# myPLA_Tester_shield.net
KiCad netlist of a schematic drawn in EAGLE
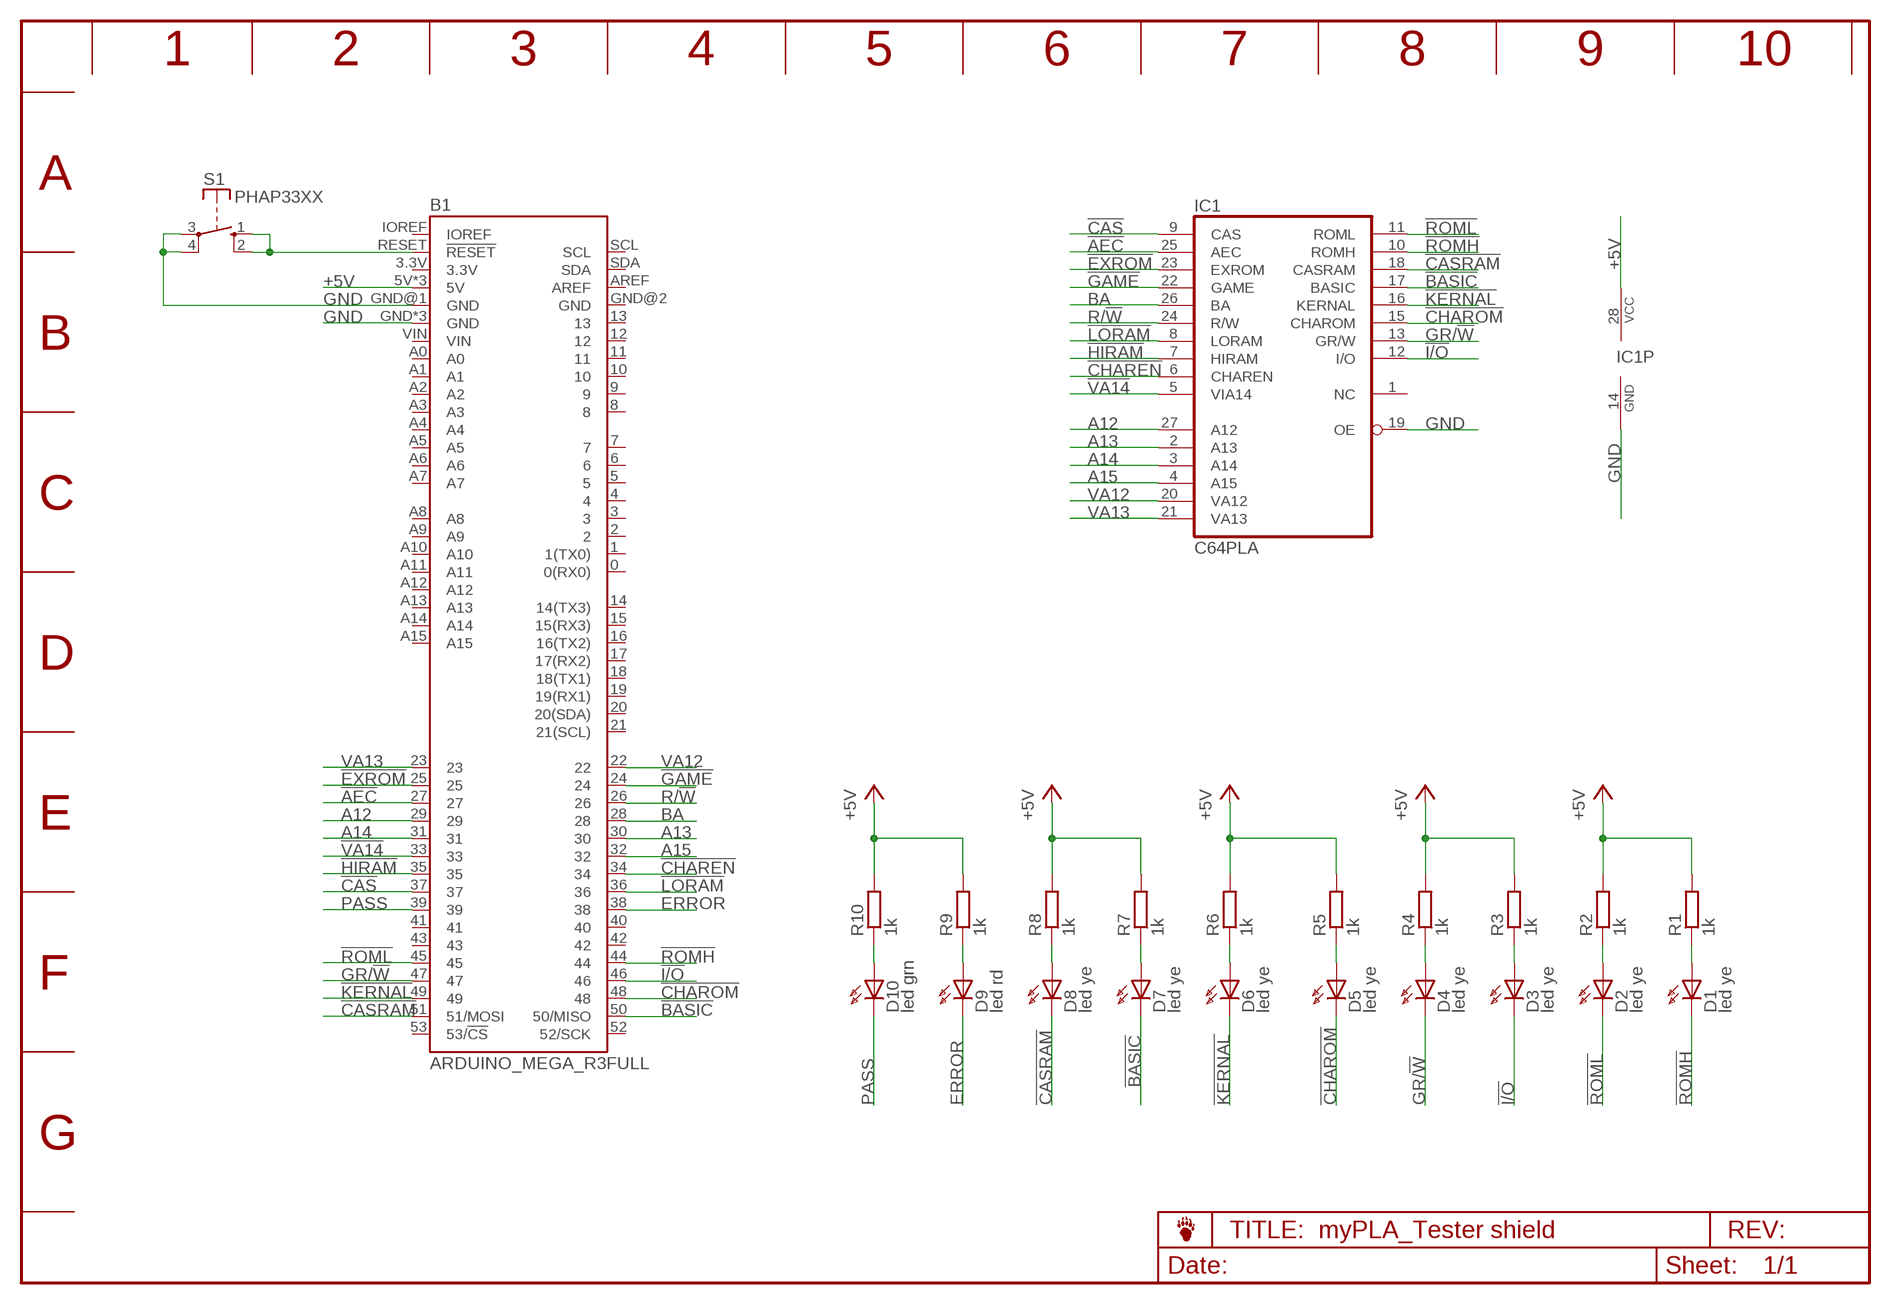
[diagram p0: schematic, sheet 1]

(export (version "E")
  (design (tool "Eeschema 10.0.6"))
  (components
    (comp (ref "B1")
      (value "ARDUINO_MEGA_R3FULL")
      (footprint "eagle-import:ARDUINO_MEGA_NO_SILK")
      (libsource (lib "eagle-import") (part "ARDUINO_MEGA_R3FULL"))
    )
    (comp (ref "D1")
      (value "led ye")
      (footprint "eagle-import:LED3MM")
      (libsource (lib "eagle-import") (part "LED3MMS"))
    )
    (comp (ref "D2")
      (value "led ye")
      (footprint "eagle-import:LED3MM")
      (libsource (lib "eagle-import") (part "LED3MMS"))
    )
    (comp (ref "D3")
      (value "led ye")
      (footprint "eagle-import:LED3MM")
      (libsource (lib "eagle-import") (part "LED3MMS"))
    )
    (comp (ref "D4")
      (value "led ye")
      (footprint "eagle-import:LED3MM")
      (libsource (lib "eagle-import") (part "LED3MMS"))
    )
    (comp (ref "D5")
      (value "led ye")
      (footprint "eagle-import:LED3MM")
      (libsource (lib "eagle-import") (part "LED3MMS"))
    )
    (comp (ref "D6")
      (value "led ye")
      (footprint "eagle-import:LED3MM")
      (libsource (lib "eagle-import") (part "LED3MMS"))
    )
    (comp (ref "D7")
      (value "led ye")
      (footprint "eagle-import:LED3MM")
      (libsource (lib "eagle-import") (part "LED3MMS"))
    )
    (comp (ref "D8")
      (value "led ye")
      (footprint "eagle-import:LED3MM")
      (libsource (lib "eagle-import") (part "LED3MMS"))
    )
    (comp (ref "D9")
      (value "led rd")
      (footprint "eagle-import:LED3MM")
      (libsource (lib "eagle-import") (part "LED3MMS"))
    )
    (comp (ref "D10")
      (value "led grn")
      (footprint "eagle-import:LED3MM")
      (libsource (lib "eagle-import") (part "LED3MMS"))
    )
    (comp (ref "IC1")
      (value "C64PLA")
      (footprint "eagle-import:DIL28")
      (libsource (lib "eagle-import") (part "C64PLA"))
    )
    (comp (ref "R1")
      (value "1k")
      (footprint "eagle-import:0207_10")
      (libsource (lib "eagle-import") (part "R-EU_0207/10"))
    )
    (comp (ref "R2")
      (value "1k")
      (footprint "eagle-import:0207_10")
      (libsource (lib "eagle-import") (part "R-EU_0207/10"))
    )
    (comp (ref "R3")
      (value "1k")
      (footprint "eagle-import:0207_10")
      (libsource (lib "eagle-import") (part "R-EU_0207/10"))
    )
    (comp (ref "R4")
      (value "1k")
      (footprint "eagle-import:0207_10")
      (libsource (lib "eagle-import") (part "R-EU_0207/10"))
    )
    (comp (ref "R5")
      (value "1k")
      (footprint "eagle-import:0207_10")
      (libsource (lib "eagle-import") (part "R-EU_0207/10"))
    )
    (comp (ref "R6")
      (value "1k")
      (footprint "eagle-import:0207_10")
      (libsource (lib "eagle-import") (part "R-EU_0207/10"))
    )
    (comp (ref "R7")
      (value "1k")
      (footprint "eagle-import:0207_10")
      (libsource (lib "eagle-import") (part "R-EU_0207/10"))
    )
    (comp (ref "R8")
      (value "1k")
      (footprint "eagle-import:0207_10")
      (libsource (lib "eagle-import") (part "R-EU_0207/10"))
    )
    (comp (ref "R9")
      (value "1k")
      (footprint "eagle-import:0207_10")
      (libsource (lib "eagle-import") (part "R-EU_0207/10"))
    )
    (comp (ref "R10")
      (value "1k")
      (footprint "eagle-import:0207_10")
      (libsource (lib "eagle-import") (part "R-EU_0207/10"))
    )
    (comp (ref "S1")
      (value "PHAP33XX")
      (footprint "eagle-import:PHAP33XX")
      (libsource (lib "eagle-import") (part "PHAP33XX"))
    )
  )
  (nets
    (net (code "1") (name "+5V") (class "Default")
      (node (ref "B1") (pin "5V") (pinfunction "5V_5V") (pintype "bidirectional"))
      (node (ref "B1") (pin "5V@1") (pinfunction "5V_5V@1") (pintype "bidirectional"))
      (node (ref "B1") (pin "5V@2") (pinfunction "5V_5V@2") (pintype "bidirectional"))
      (node (ref "IC1") (pin "28") (pinfunction "VCC_28") (pintype "power_in"))
      (node (ref "R1") (pin "2") (pinfunction "2_2") (pintype "passive"))
      (node (ref "R10") (pin "2") (pinfunction "2_2") (pintype "passive"))
      (node (ref "R2") (pin "2") (pinfunction "2_2") (pintype "passive"))
      (node (ref "R3") (pin "2") (pinfunction "2_2") (pintype "passive"))
      (node (ref "R4") (pin "2") (pinfunction "2_2") (pintype "passive"))
      (node (ref "R5") (pin "2") (pinfunction "2_2") (pintype "passive"))
      (node (ref "R6") (pin "2") (pinfunction "2_2") (pintype "passive"))
      (node (ref "R7") (pin "2") (pinfunction "2_2") (pintype "passive"))
      (node (ref "R8") (pin "2") (pinfunction "2_2") (pintype "passive"))
      (node (ref "R9") (pin "2") (pinfunction "2_2") (pintype "passive"))
    )
    (net (code "2") (name "/A12") (class "Default")
      (node (ref "B1") (pin "29") (pinfunction "29_29") (pintype "bidirectional"))
      (node (ref "IC1") (pin "27") (pinfunction "A12_27") (pintype "input"))
    )
    (net (code "3") (name "/A13") (class "Default")
      (node (ref "B1") (pin "30") (pinfunction "30_30") (pintype "bidirectional"))
      (node (ref "IC1") (pin "2") (pinfunction "A13_2") (pintype "input"))
    )
    (net (code "4") (name "/A14") (class "Default")
      (node (ref "B1") (pin "31") (pinfunction "31_31") (pintype "bidirectional"))
      (node (ref "IC1") (pin "3") (pinfunction "A14_3") (pintype "input"))
    )
    (net (code "5") (name "/A15") (class "Default")
      (node (ref "B1") (pin "32") (pinfunction "32_32") (pintype "bidirectional"))
      (node (ref "IC1") (pin "4") (pinfunction "A15_4") (pintype "input"))
    )
    (net (code "6") (name "/BA") (class "Default")
      (node (ref "B1") (pin "28") (pinfunction "28_28") (pintype "bidirectional"))
      (node (ref "IC1") (pin "26") (pinfunction "BA_26") (pintype "input"))
    )
    (net (code "7") (name "/ERROR") (class "Default")
      (node (ref "B1") (pin "38") (pinfunction "38_38") (pintype "bidirectional"))
      (node (ref "D9") (pin "K") (pinfunction "C_K") (pintype "passive"))
    )
    (net (code "8") (name "/GND") (class "Default")
      (node (ref "B1") (pin "GND") (pinfunction "GND_GND") (pintype "bidirectional"))
      (node (ref "B1") (pin "GND@1") (pinfunction "GND_GND@1") (pintype "bidirectional"))
      (node (ref "B1") (pin "GND@3") (pinfunction "GND_GND@3") (pintype "bidirectional"))
      (node (ref "B1") (pin "GND@4") (pinfunction "GND_GND@4") (pintype "bidirectional"))
      (node (ref "IC1") (pin "14") (pinfunction "GND_14") (pintype "power_in"))
      (node (ref "IC1") (pin "19") (pinfunction "OE_19") (pintype "input"))
      (node (ref "S1") (pin "3") (pinfunction "P_3") (pintype "passive"))
      (node (ref "S1") (pin "4") (pinfunction "P_4") (pintype "passive"))
    )
    (net (code "9") (name "/GR{slash}~{W}") (class "Default")
      (node (ref "B1") (pin "47") (pinfunction "47_47") (pintype "bidirectional"))
      (node (ref "D4") (pin "K") (pinfunction "C_K") (pintype "passive"))
      (node (ref "IC1") (pin "13") (pinfunction "GR/W_13") (pintype "tri_state"))
    )
    (net (code "10") (name "/PASS") (class "Default")
      (node (ref "B1") (pin "39") (pinfunction "39_39") (pintype "bidirectional"))
      (node (ref "D10") (pin "K") (pinfunction "C_K") (pintype "passive"))
    )
    (net (code "11") (name "/R{slash}~{W}") (class "Default")
      (node (ref "B1") (pin "26") (pinfunction "26_26") (pintype "bidirectional"))
      (node (ref "IC1") (pin "24") (pinfunction "R/W_24") (pintype "input"))
    )
    (net (code "12") (name "/VA12") (class "Default")
      (node (ref "B1") (pin "22") (pinfunction "22_22") (pintype "bidirectional"))
      (node (ref "IC1") (pin "20") (pinfunction "VA12_20") (pintype "input"))
    )
    (net (code "13") (name "/VA13") (class "Default")
      (node (ref "B1") (pin "23") (pinfunction "23_23") (pintype "bidirectional"))
      (node (ref "IC1") (pin "21") (pinfunction "VA13_21") (pintype "input"))
    )
    (net (code "14") (name "/~{AEC}") (class "Default")
      (node (ref "B1") (pin "27") (pinfunction "27_27") (pintype "bidirectional"))
      (node (ref "IC1") (pin "25") (pinfunction "AEC_25") (pintype "input"))
    )
    (net (code "15") (name "/~{BASIC}") (class "Default")
      (node (ref "B1") (pin "50") (pinfunction "50/MISO_50") (pintype "bidirectional"))
      (node (ref "D7") (pin "K") (pinfunction "C_K") (pintype "passive"))
      (node (ref "IC1") (pin "17") (pinfunction "BASIC_17") (pintype "tri_state"))
    )
    (net (code "16") (name "/~{CASRAM}") (class "Default")
      (node (ref "B1") (pin "51") (pinfunction "51/MOSI_51") (pintype "bidirectional"))
      (node (ref "D8") (pin "K") (pinfunction "C_K") (pintype "passive"))
      (node (ref "IC1") (pin "18") (pinfunction "CASRAM_18") (pintype "tri_state"))
    )
    (net (code "17") (name "/~{CAS}") (class "Default")
      (node (ref "B1") (pin "37") (pinfunction "37_37") (pintype "bidirectional"))
      (node (ref "IC1") (pin "9") (pinfunction "CAS_9") (pintype "input"))
    )
    (net (code "18") (name "/~{CHAREN}") (class "Default")
      (node (ref "B1") (pin "34") (pinfunction "34_34") (pintype "bidirectional"))
      (node (ref "IC1") (pin "6") (pinfunction "CHAREN_6") (pintype "input"))
    )
    (net (code "19") (name "/~{CHAROM}") (class "Default")
      (node (ref "B1") (pin "48") (pinfunction "48_48") (pintype "bidirectional"))
      (node (ref "D5") (pin "K") (pinfunction "C_K") (pintype "passive"))
      (node (ref "IC1") (pin "15") (pinfunction "CHAROM_15") (pintype "tri_state"))
    )
    (net (code "20") (name "/~{EXROM}") (class "Default")
      (node (ref "B1") (pin "25") (pinfunction "25_25") (pintype "bidirectional"))
      (node (ref "IC1") (pin "23") (pinfunction "EXROM_23") (pintype "input"))
    )
    (net (code "21") (name "/~{GAME}") (class "Default")
      (node (ref "B1") (pin "24") (pinfunction "24_24") (pintype "bidirectional"))
      (node (ref "IC1") (pin "22") (pinfunction "GAME_22") (pintype "input"))
    )
    (net (code "22") (name "/~{HIRAM}") (class "Default")
      (node (ref "B1") (pin "35") (pinfunction "35_35") (pintype "bidirectional"))
      (node (ref "IC1") (pin "7") (pinfunction "HIRAM_7") (pintype "input"))
    )
    (net (code "23") (name "/~{I{slash}O}") (class "Default")
      (node (ref "B1") (pin "46") (pinfunction "46_46") (pintype "bidirectional"))
      (node (ref "D3") (pin "K") (pinfunction "C_K") (pintype "passive"))
      (node (ref "IC1") (pin "12") (pinfunction "I/O_12") (pintype "tri_state"))
    )
    (net (code "24") (name "/~{KERNAL}") (class "Default")
      (node (ref "B1") (pin "49") (pinfunction "49_49") (pintype "bidirectional"))
      (node (ref "D6") (pin "K") (pinfunction "C_K") (pintype "passive"))
      (node (ref "IC1") (pin "16") (pinfunction "KERNAL_16") (pintype "tri_state"))
    )
    (net (code "25") (name "/~{LORAM}") (class "Default")
      (node (ref "B1") (pin "36") (pinfunction "36_36") (pintype "bidirectional"))
      (node (ref "IC1") (pin "8") (pinfunction "LORAM_8") (pintype "input"))
    )
    (net (code "26") (name "/~{ROMH}") (class "Default")
      (node (ref "B1") (pin "44") (pinfunction "44_44") (pintype "bidirectional"))
      (node (ref "D1") (pin "K") (pinfunction "C_K") (pintype "passive"))
      (node (ref "IC1") (pin "10") (pinfunction "ROMH_10") (pintype "tri_state"))
    )
    (net (code "27") (name "/~{ROML}") (class "Default")
      (node (ref "B1") (pin "45") (pinfunction "45_45") (pintype "bidirectional"))
      (node (ref "D2") (pin "K") (pinfunction "C_K") (pintype "passive"))
      (node (ref "IC1") (pin "11") (pinfunction "ROML_11") (pintype "tri_state"))
    )
    (net (code "28") (name "/~{VA14}") (class "Default")
      (node (ref "B1") (pin "33") (pinfunction "33_33") (pintype "bidirectional"))
      (node (ref "IC1") (pin "5") (pinfunction "VIA14_5") (pintype "input"))
    )
    (net (code "29") (name "Net-(B1-~{RESET})") (class "Default")
      (node (ref "B1") (pin "RESET") (pinfunction "~{RESET}_RESET") (pintype "bidirectional"))
      (node (ref "S1") (pin "1") (pinfunction "S_1") (pintype "passive"))
      (node (ref "S1") (pin "2") (pinfunction "S_2") (pintype "passive"))
    )
    (net (code "30") (name "Net-(D1-PadA)") (class "Default")
      (node (ref "D1") (pin "A") (pinfunction "A_A") (pintype "passive"))
      (node (ref "R1") (pin "1") (pinfunction "1_1") (pintype "passive"))
    )
    (net (code "31") (name "Net-(D2-PadA)") (class "Default")
      (node (ref "D2") (pin "A") (pinfunction "A_A") (pintype "passive"))
      (node (ref "R2") (pin "1") (pinfunction "1_1") (pintype "passive"))
    )
    (net (code "32") (name "Net-(D3-PadA)") (class "Default")
      (node (ref "D3") (pin "A") (pinfunction "A_A") (pintype "passive"))
      (node (ref "R3") (pin "1") (pinfunction "1_1") (pintype "passive"))
    )
    (net (code "33") (name "Net-(D4-PadA)") (class "Default")
      (node (ref "D4") (pin "A") (pinfunction "A_A") (pintype "passive"))
      (node (ref "R4") (pin "1") (pinfunction "1_1") (pintype "passive"))
    )
    (net (code "34") (name "Net-(D5-PadA)") (class "Default")
      (node (ref "D5") (pin "A") (pinfunction "A_A") (pintype "passive"))
      (node (ref "R5") (pin "1") (pinfunction "1_1") (pintype "passive"))
    )
    (net (code "35") (name "Net-(D6-PadA)") (class "Default")
      (node (ref "D6") (pin "A") (pinfunction "A_A") (pintype "passive"))
      (node (ref "R6") (pin "1") (pinfunction "1_1") (pintype "passive"))
    )
    (net (code "36") (name "Net-(D7-PadA)") (class "Default")
      (node (ref "D7") (pin "A") (pinfunction "A_A") (pintype "passive"))
      (node (ref "R7") (pin "1") (pinfunction "1_1") (pintype "passive"))
    )
    (net (code "37") (name "Net-(D8-PadA)") (class "Default")
      (node (ref "D8") (pin "A") (pinfunction "A_A") (pintype "passive"))
      (node (ref "R8") (pin "1") (pinfunction "1_1") (pintype "passive"))
    )
    (net (code "38") (name "Net-(D9-PadA)") (class "Default")
      (node (ref "D9") (pin "A") (pinfunction "A_A") (pintype "passive"))
      (node (ref "R9") (pin "1") (pinfunction "1_1") (pintype "passive"))
    )
    (net (code "39") (name "Net-(D10-PadA)") (class "Default")
      (node (ref "D10") (pin "A") (pinfunction "A_A") (pintype "passive"))
      (node (ref "R10") (pin "1") (pinfunction "1_1") (pintype "passive"))
    )
    (net (code "40") (name "unconnected-(B1-0(RX0)-Pad0)") (class "Default")
      (node (ref "B1") (pin "0") (pinfunction "0(RX0)_0") (pintype "bidirectional"))
    )
    (net (code "41") (name "unconnected-(B1-1(TX0)-Pad1)") (class "Default")
      (node (ref "B1") (pin "1") (pinfunction "1(TX0)_1") (pintype "bidirectional"))
    )
    (net (code "42") (name "unconnected-(B1-14(TX3)-Pad14)") (class "Default")
      (node (ref "B1") (pin "14") (pinfunction "14(TX3)_14") (pintype "bidirectional"))
    )
    (net (code "43") (name "unconnected-(B1-15(RX3)-Pad15)") (class "Default")
      (node (ref "B1") (pin "15") (pinfunction "15(RX3)_15") (pintype "bidirectional"))
    )
    (net (code "44") (name "unconnected-(B1-16(TX2)-Pad16)") (class "Default")
      (node (ref "B1") (pin "16") (pinfunction "16(TX2)_16") (pintype "bidirectional"))
    )
    (net (code "45") (name "unconnected-(B1-17(RX2)-Pad17)") (class "Default")
      (node (ref "B1") (pin "17") (pinfunction "17(RX2)_17") (pintype "bidirectional"))
    )
    (net (code "46") (name "unconnected-(B1-18(TX1)-Pad18)") (class "Default")
      (node (ref "B1") (pin "18") (pinfunction "18(TX1)_18") (pintype "bidirectional"))
    )
    (net (code "47") (name "unconnected-(B1-19(RX1)-Pad19)") (class "Default")
      (node (ref "B1") (pin "19") (pinfunction "19(RX1)_19") (pintype "bidirectional"))
    )
    (net (code "48") (name "unconnected-(B1-20(SDA)-Pad20)") (class "Default")
      (node (ref "B1") (pin "20") (pinfunction "20(SDA)_20") (pintype "bidirectional"))
    )
    (net (code "49") (name "unconnected-(B1-21(SCL)-Pad21)") (class "Default")
      (node (ref "B1") (pin "21") (pinfunction "21(SCL)_21") (pintype "bidirectional"))
    )
    (net (code "50") (name "unconnected-(B1-52{slash}SCK-Pad52)") (class "Default")
      (node (ref "B1") (pin "52") (pinfunction "52/SCK_52") (pintype "bidirectional"))
    )
    (net (code "51") (name "unconnected-(B1-53{slash}~{CS}-Pad53)") (class "Default")
      (node (ref "B1") (pin "53") (pinfunction "53/~{CS}_53") (pintype "bidirectional"))
    )
    (net (code "52") (name "unconnected-(B1-GND-PadGND@2)") (class "Default")
      (node (ref "B1") (pin "GND@2") (pinfunction "GND_GND@2") (pintype "bidirectional"))
    )
    (net (code "53") (name "unconnected-(B1-Pad2)") (class "Default")
      (node (ref "B1") (pin "2") (pinfunction "2_2") (pintype "bidirectional"))
    )
    (net (code "54") (name "unconnected-(B1-Pad3)") (class "Default")
      (node (ref "B1") (pin "3") (pinfunction "3_3") (pintype "bidirectional"))
    )
    (net (code "55") (name "unconnected-(B1-Pad3.3V)") (class "Default")
      (node (ref "B1") (pin "3.3V") (pinfunction "3.3V_3.3V") (pintype "bidirectional"))
    )
    (net (code "56") (name "unconnected-(B1-Pad4)") (class "Default")
      (node (ref "B1") (pin "4") (pinfunction "4_4") (pintype "bidirectional"))
    )
    (net (code "57") (name "unconnected-(B1-Pad5)") (class "Default")
      (node (ref "B1") (pin "5") (pinfunction "5_5") (pintype "bidirectional"))
    )
    (net (code "58") (name "unconnected-(B1-Pad6)") (class "Default")
      (node (ref "B1") (pin "6") (pinfunction "6_6") (pintype "bidirectional"))
    )
    (net (code "59") (name "unconnected-(B1-Pad7)") (class "Default")
      (node (ref "B1") (pin "7") (pinfunction "7_7") (pintype "bidirectional"))
    )
    (net (code "60") (name "unconnected-(B1-Pad8)") (class "Default")
      (node (ref "B1") (pin "8") (pinfunction "8_8") (pintype "bidirectional"))
    )
    (net (code "61") (name "unconnected-(B1-Pad9)") (class "Default")
      (node (ref "B1") (pin "9") (pinfunction "9_9") (pintype "bidirectional"))
    )
    (net (code "62") (name "unconnected-(B1-Pad10)") (class "Default")
      (node (ref "B1") (pin "10") (pinfunction "10_10") (pintype "bidirectional"))
    )
    (net (code "63") (name "unconnected-(B1-Pad11)") (class "Default")
      (node (ref "B1") (pin "11") (pinfunction "11_11") (pintype "bidirectional"))
    )
    (net (code "64") (name "unconnected-(B1-Pad12)") (class "Default")
      (node (ref "B1") (pin "12") (pinfunction "12_12") (pintype "bidirectional"))
    )
    (net (code "65") (name "unconnected-(B1-Pad13)") (class "Default")
      (node (ref "B1") (pin "13") (pinfunction "13_13") (pintype "bidirectional"))
    )
    (net (code "66") (name "unconnected-(B1-Pad40)") (class "Default")
      (node (ref "B1") (pin "40") (pinfunction "40_40") (pintype "bidirectional"))
    )
    (net (code "67") (name "unconnected-(B1-Pad41)") (class "Default")
      (node (ref "B1") (pin "41") (pinfunction "41_41") (pintype "bidirectional"))
    )
    (net (code "68") (name "unconnected-(B1-Pad42)") (class "Default")
      (node (ref "B1") (pin "42") (pinfunction "42_42") (pintype "bidirectional"))
    )
    (net (code "69") (name "unconnected-(B1-Pad43)") (class "Default")
      (node (ref "B1") (pin "43") (pinfunction "43_43") (pintype "bidirectional"))
    )
    (net (code "70") (name "unconnected-(B1-PadA0)") (class "Default")
      (node (ref "B1") (pin "A0") (pinfunction "A0_A0") (pintype "bidirectional"))
    )
    (net (code "71") (name "unconnected-(B1-PadA1)") (class "Default")
      (node (ref "B1") (pin "A1") (pinfunction "A1_A1") (pintype "bidirectional"))
    )
    (net (code "72") (name "unconnected-(B1-PadA2)") (class "Default")
      (node (ref "B1") (pin "A2") (pinfunction "A2_A2") (pintype "bidirectional"))
    )
    (net (code "73") (name "unconnected-(B1-PadA3)") (class "Default")
      (node (ref "B1") (pin "A3") (pinfunction "A3_A3") (pintype "bidirectional"))
    )
    (net (code "74") (name "unconnected-(B1-PadA4)") (class "Default")
      (node (ref "B1") (pin "A4") (pinfunction "A4_A4") (pintype "bidirectional"))
    )
    (net (code "75") (name "unconnected-(B1-PadA5)") (class "Default")
      (node (ref "B1") (pin "A5") (pinfunction "A5_A5") (pintype "bidirectional"))
    )
    (net (code "76") (name "unconnected-(B1-PadA6)") (class "Default")
      (node (ref "B1") (pin "A6") (pinfunction "A6_A6") (pintype "bidirectional"))
    )
    (net (code "77") (name "unconnected-(B1-PadA7)") (class "Default")
      (node (ref "B1") (pin "A7") (pinfunction "A7_A7") (pintype "bidirectional"))
    )
    (net (code "78") (name "unconnected-(B1-PadA8)") (class "Default")
      (node (ref "B1") (pin "A8") (pinfunction "A8_A8") (pintype "bidirectional"))
    )
    (net (code "79") (name "unconnected-(B1-PadA9)") (class "Default")
      (node (ref "B1") (pin "A9") (pinfunction "A9_A9") (pintype "bidirectional"))
    )
    (net (code "80") (name "unconnected-(B1-PadA10)") (class "Default")
      (node (ref "B1") (pin "A10") (pinfunction "A10_A10") (pintype "bidirectional"))
    )
    (net (code "81") (name "unconnected-(B1-PadA11)") (class "Default")
      (node (ref "B1") (pin "A11") (pinfunction "A11_A11") (pintype "bidirectional"))
    )
    (net (code "82") (name "unconnected-(B1-PadA12)") (class "Default")
      (node (ref "B1") (pin "A12") (pinfunction "A12_A12") (pintype "bidirectional"))
    )
    (net (code "83") (name "unconnected-(B1-PadA13)") (class "Default")
      (node (ref "B1") (pin "A13") (pinfunction "A13_A13") (pintype "bidirectional"))
    )
    (net (code "84") (name "unconnected-(B1-PadA14)") (class "Default")
      (node (ref "B1") (pin "A14") (pinfunction "A14_A14") (pintype "bidirectional"))
    )
    (net (code "85") (name "unconnected-(B1-PadA15)") (class "Default")
      (node (ref "B1") (pin "A15") (pinfunction "A15_A15") (pintype "bidirectional"))
    )
    (net (code "86") (name "unconnected-(B1-PadAREF)") (class "Default")
      (node (ref "B1") (pin "AREF") (pinfunction "AREF_AREF") (pintype "bidirectional"))
    )
    (net (code "87") (name "unconnected-(B1-PadIOREF)") (class "Default")
      (node (ref "B1") (pin "IOREF") (pinfunction "IOREF_IOREF") (pintype "bidirectional"))
    )
    (net (code "88") (name "unconnected-(B1-PadSCL)") (class "Default")
      (node (ref "B1") (pin "SCL") (pinfunction "SCL_SCL") (pintype "bidirectional"))
    )
    (net (code "89") (name "unconnected-(B1-PadSDA)") (class "Default")
      (node (ref "B1") (pin "SDA") (pinfunction "SDA_SDA") (pintype "bidirectional"))
    )
    (net (code "90") (name "unconnected-(B1-PadVIN)") (class "Default")
      (node (ref "B1") (pin "VIN") (pinfunction "VIN_VIN") (pintype "bidirectional"))
    )
    (net (code "91") (name "unconnected-(IC1A-NC-Pad1)") (class "Default")
      (node (ref "IC1") (pin "1") (pinfunction "NC_1") (pintype "no_connect"))
    )
  )
)
